# v0_1.net
KiCad netlist of a schematic drawn in EAGLE
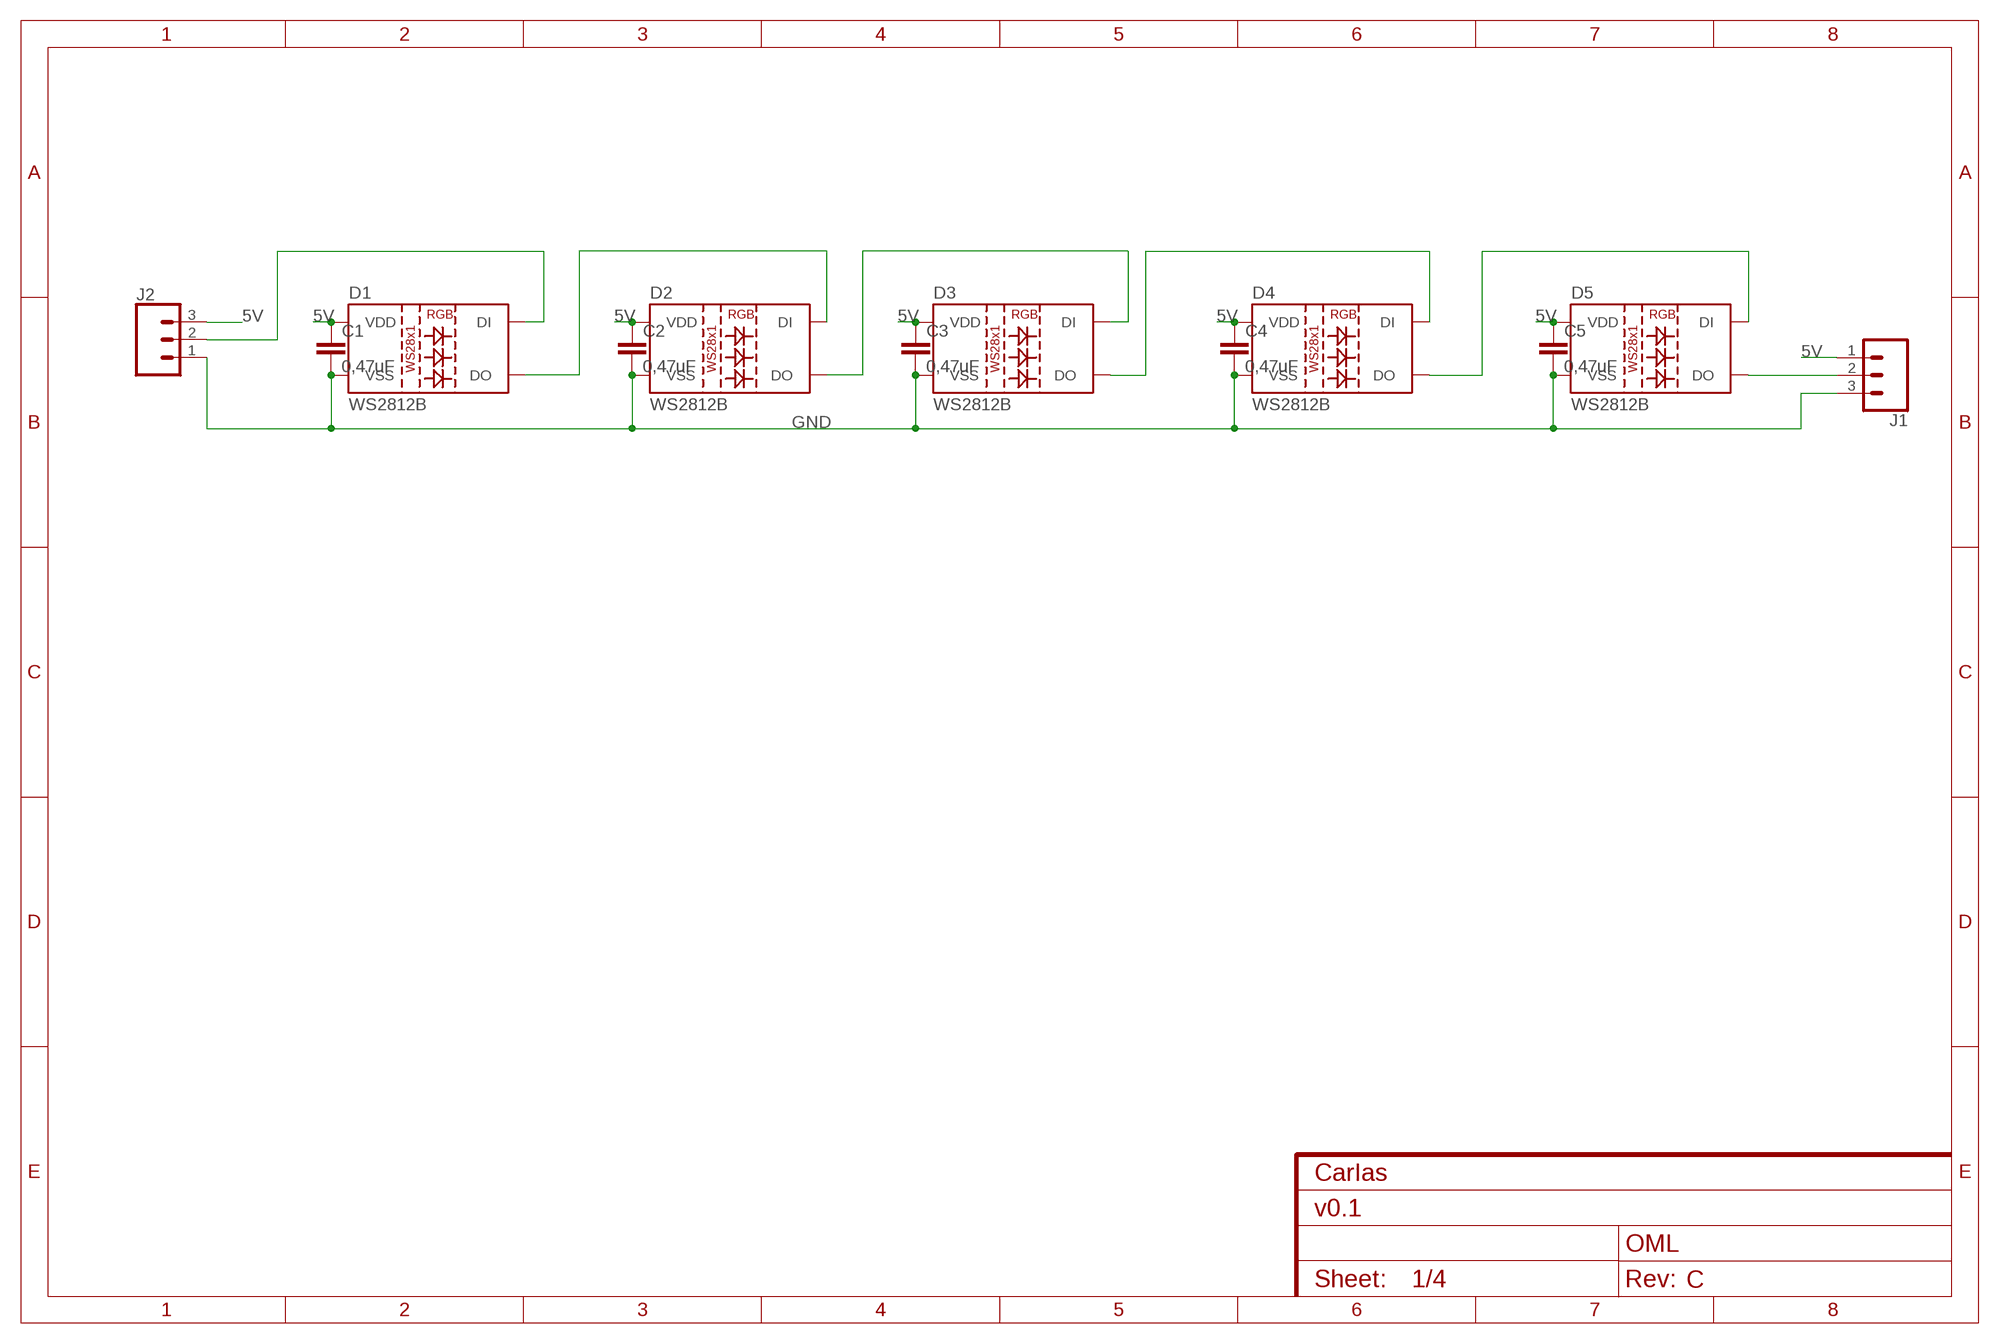
[diagram p0: schematic, sheet 1]
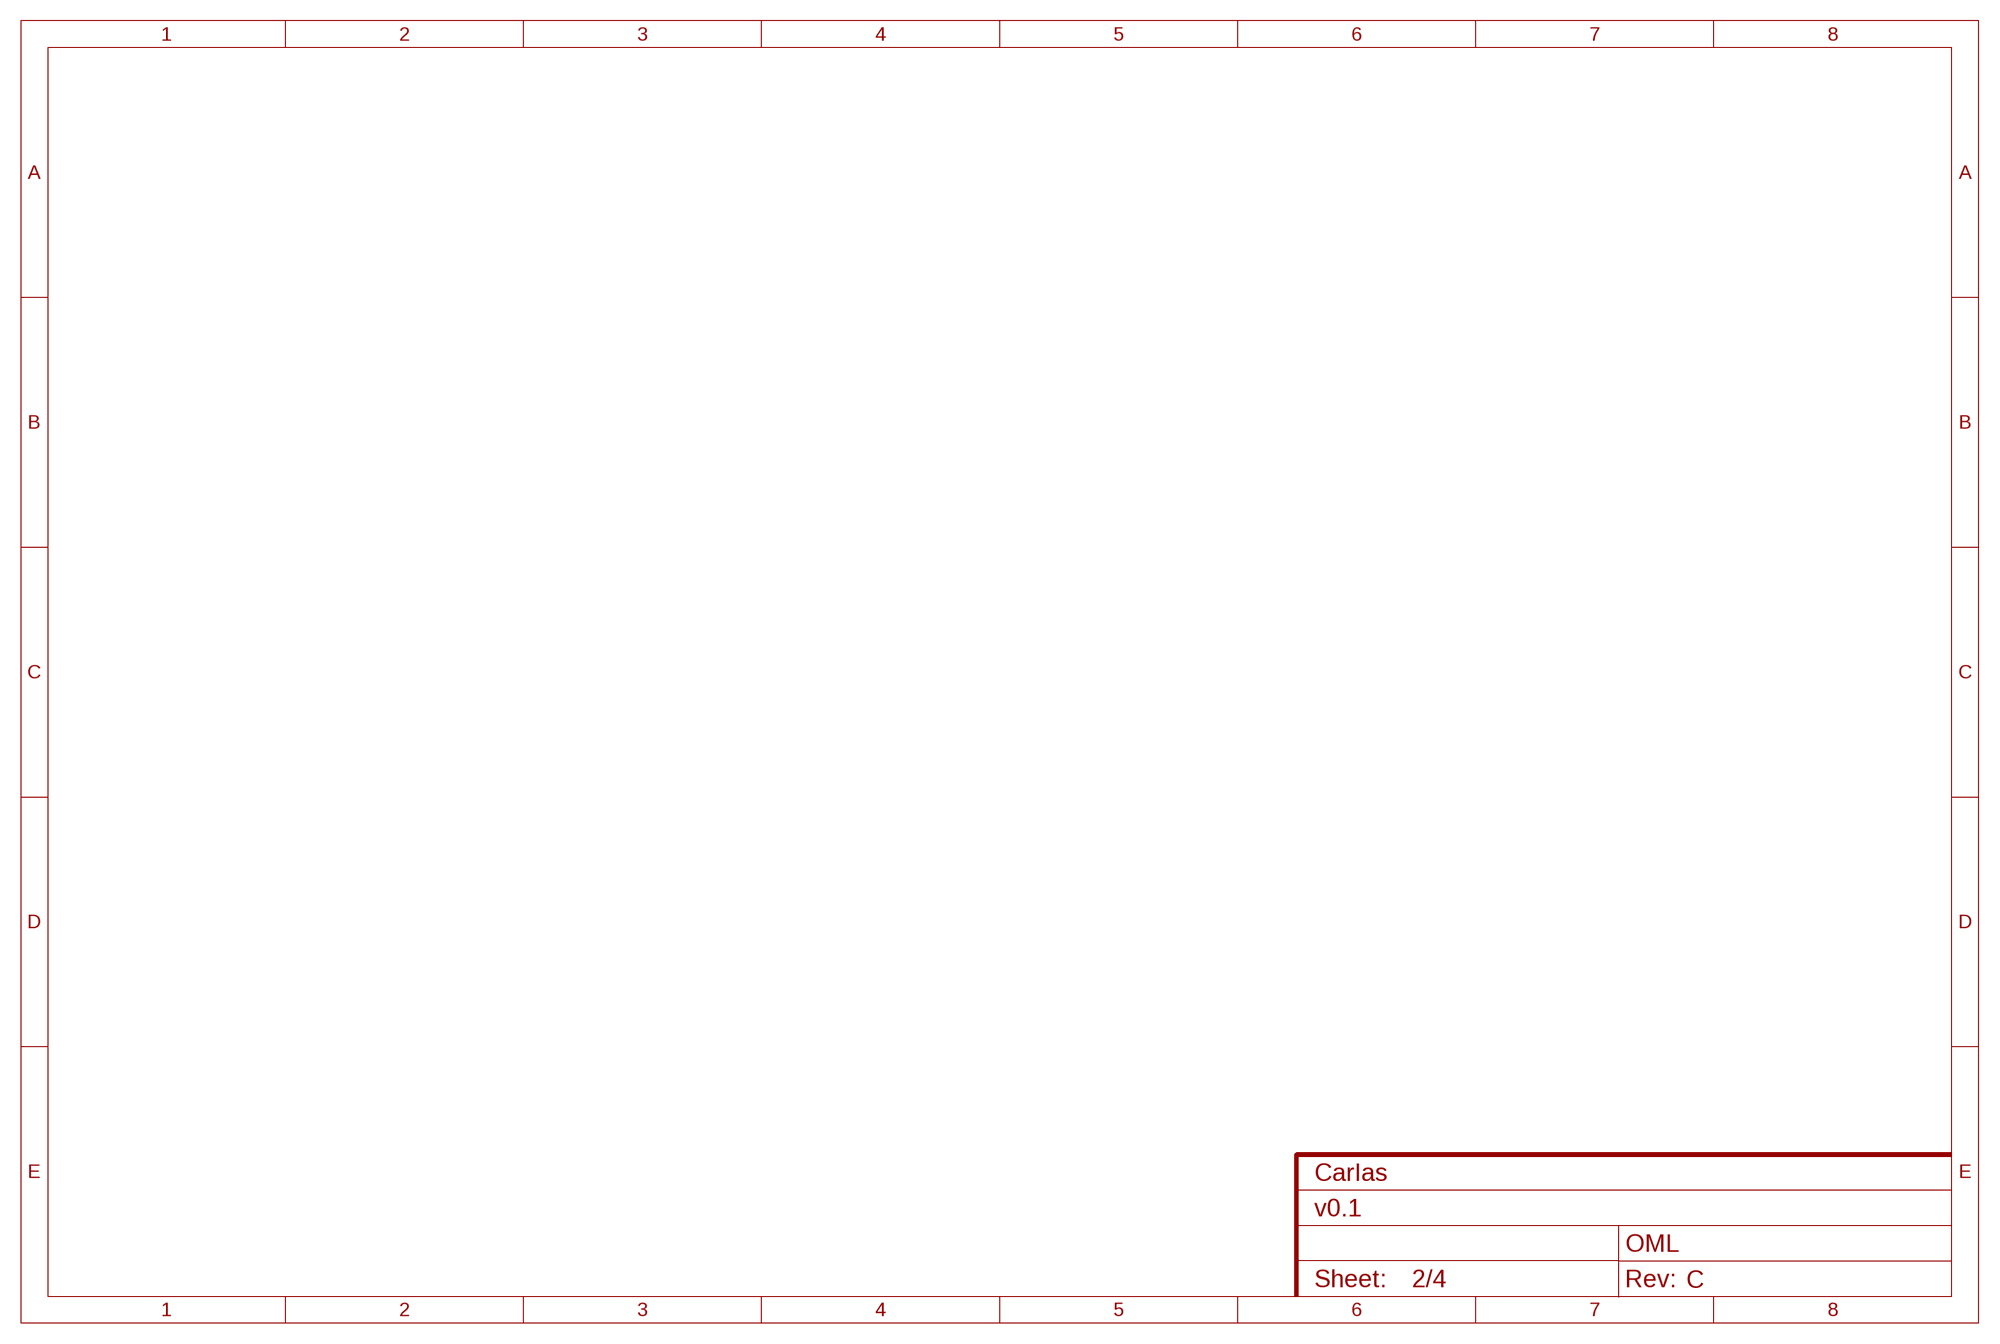
[diagram p1: schematic, sheet 2]
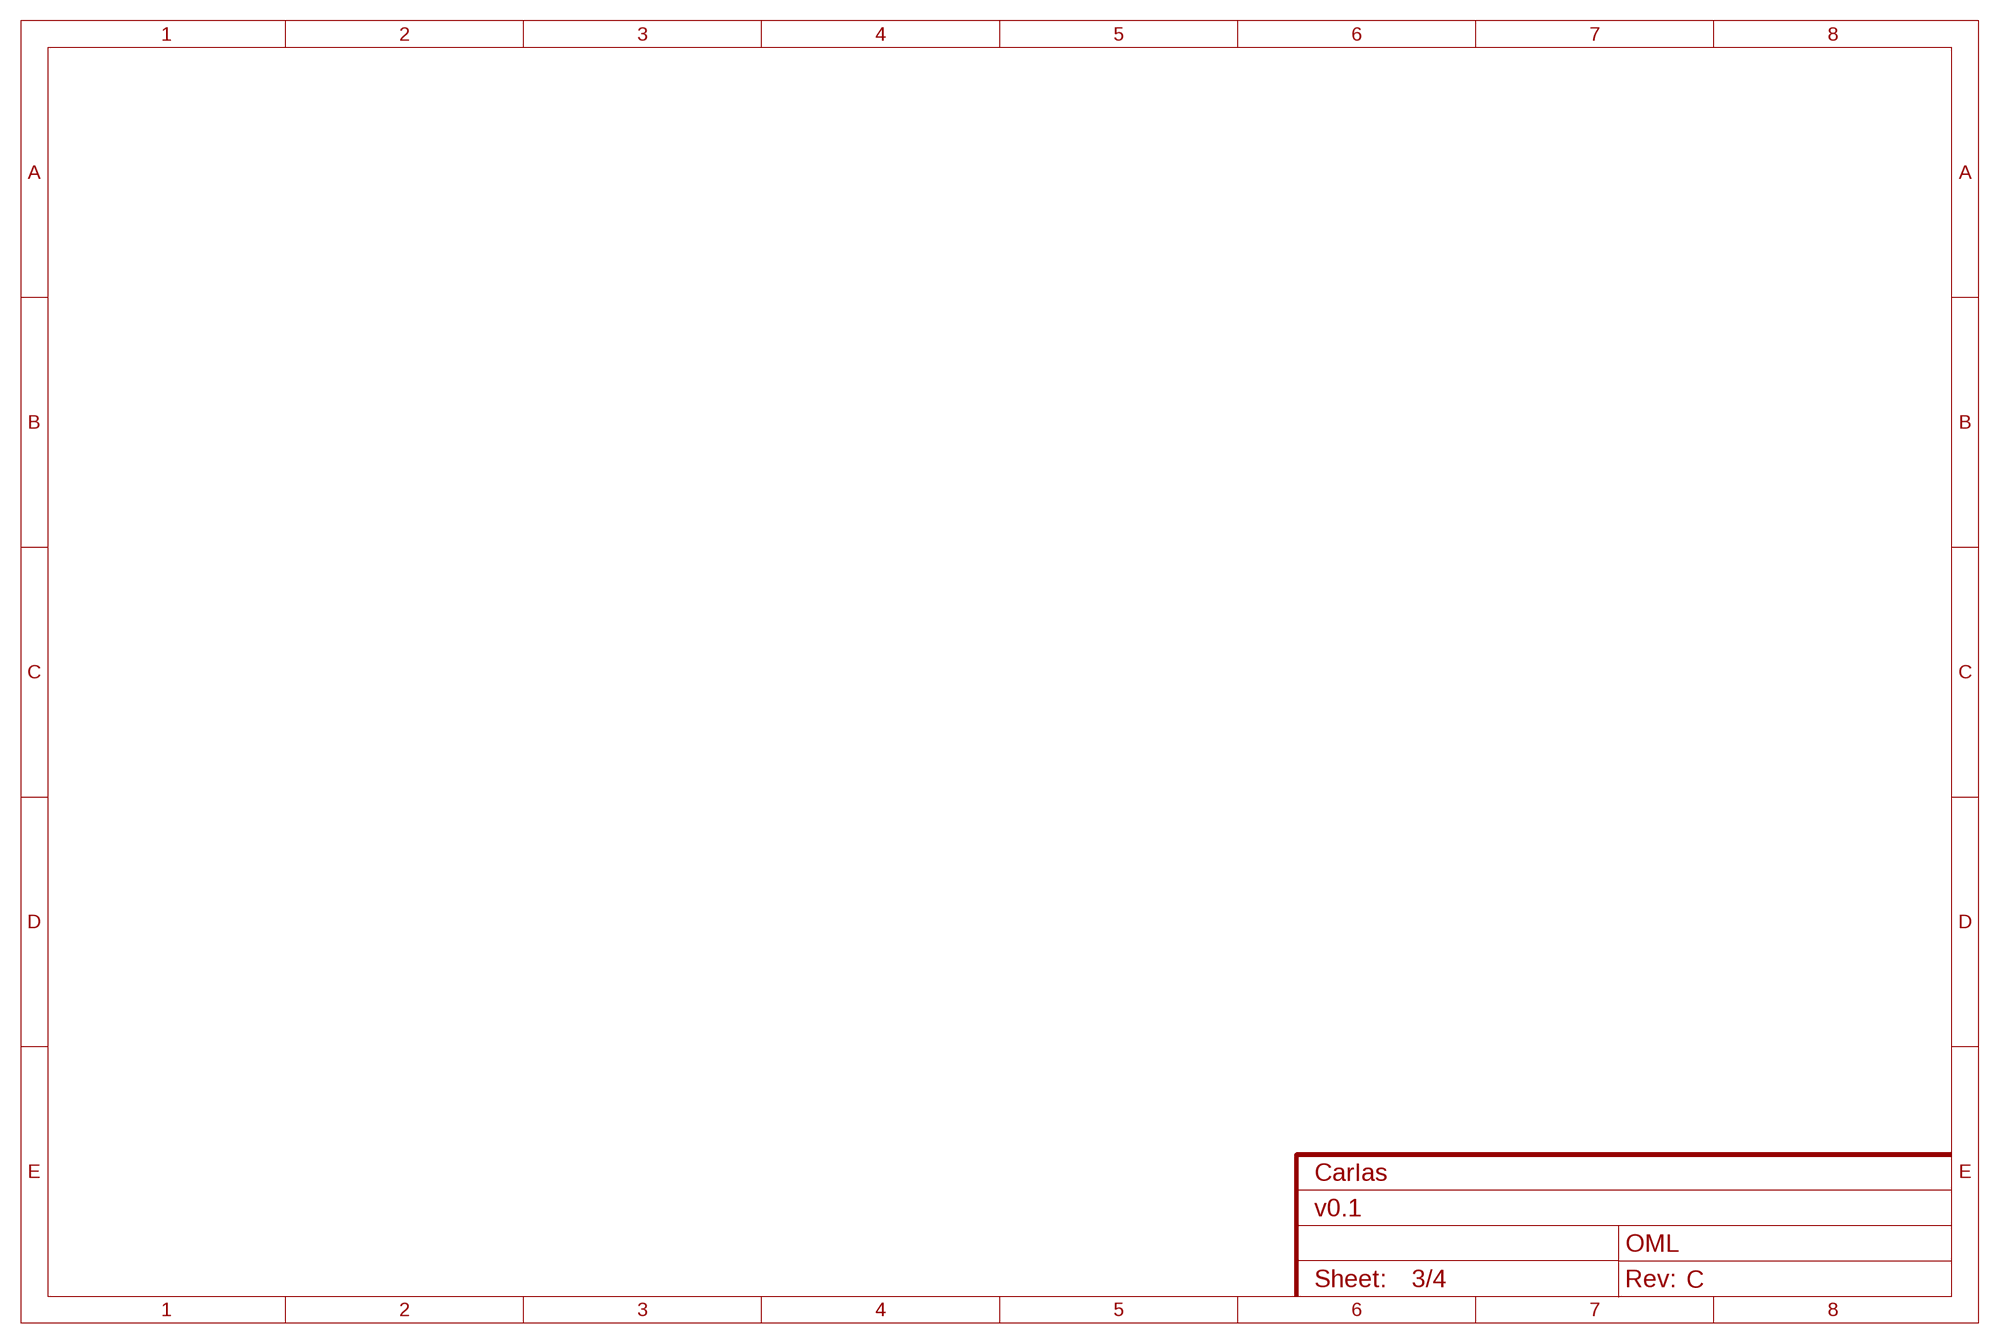
[diagram p2: schematic, sheet 3]
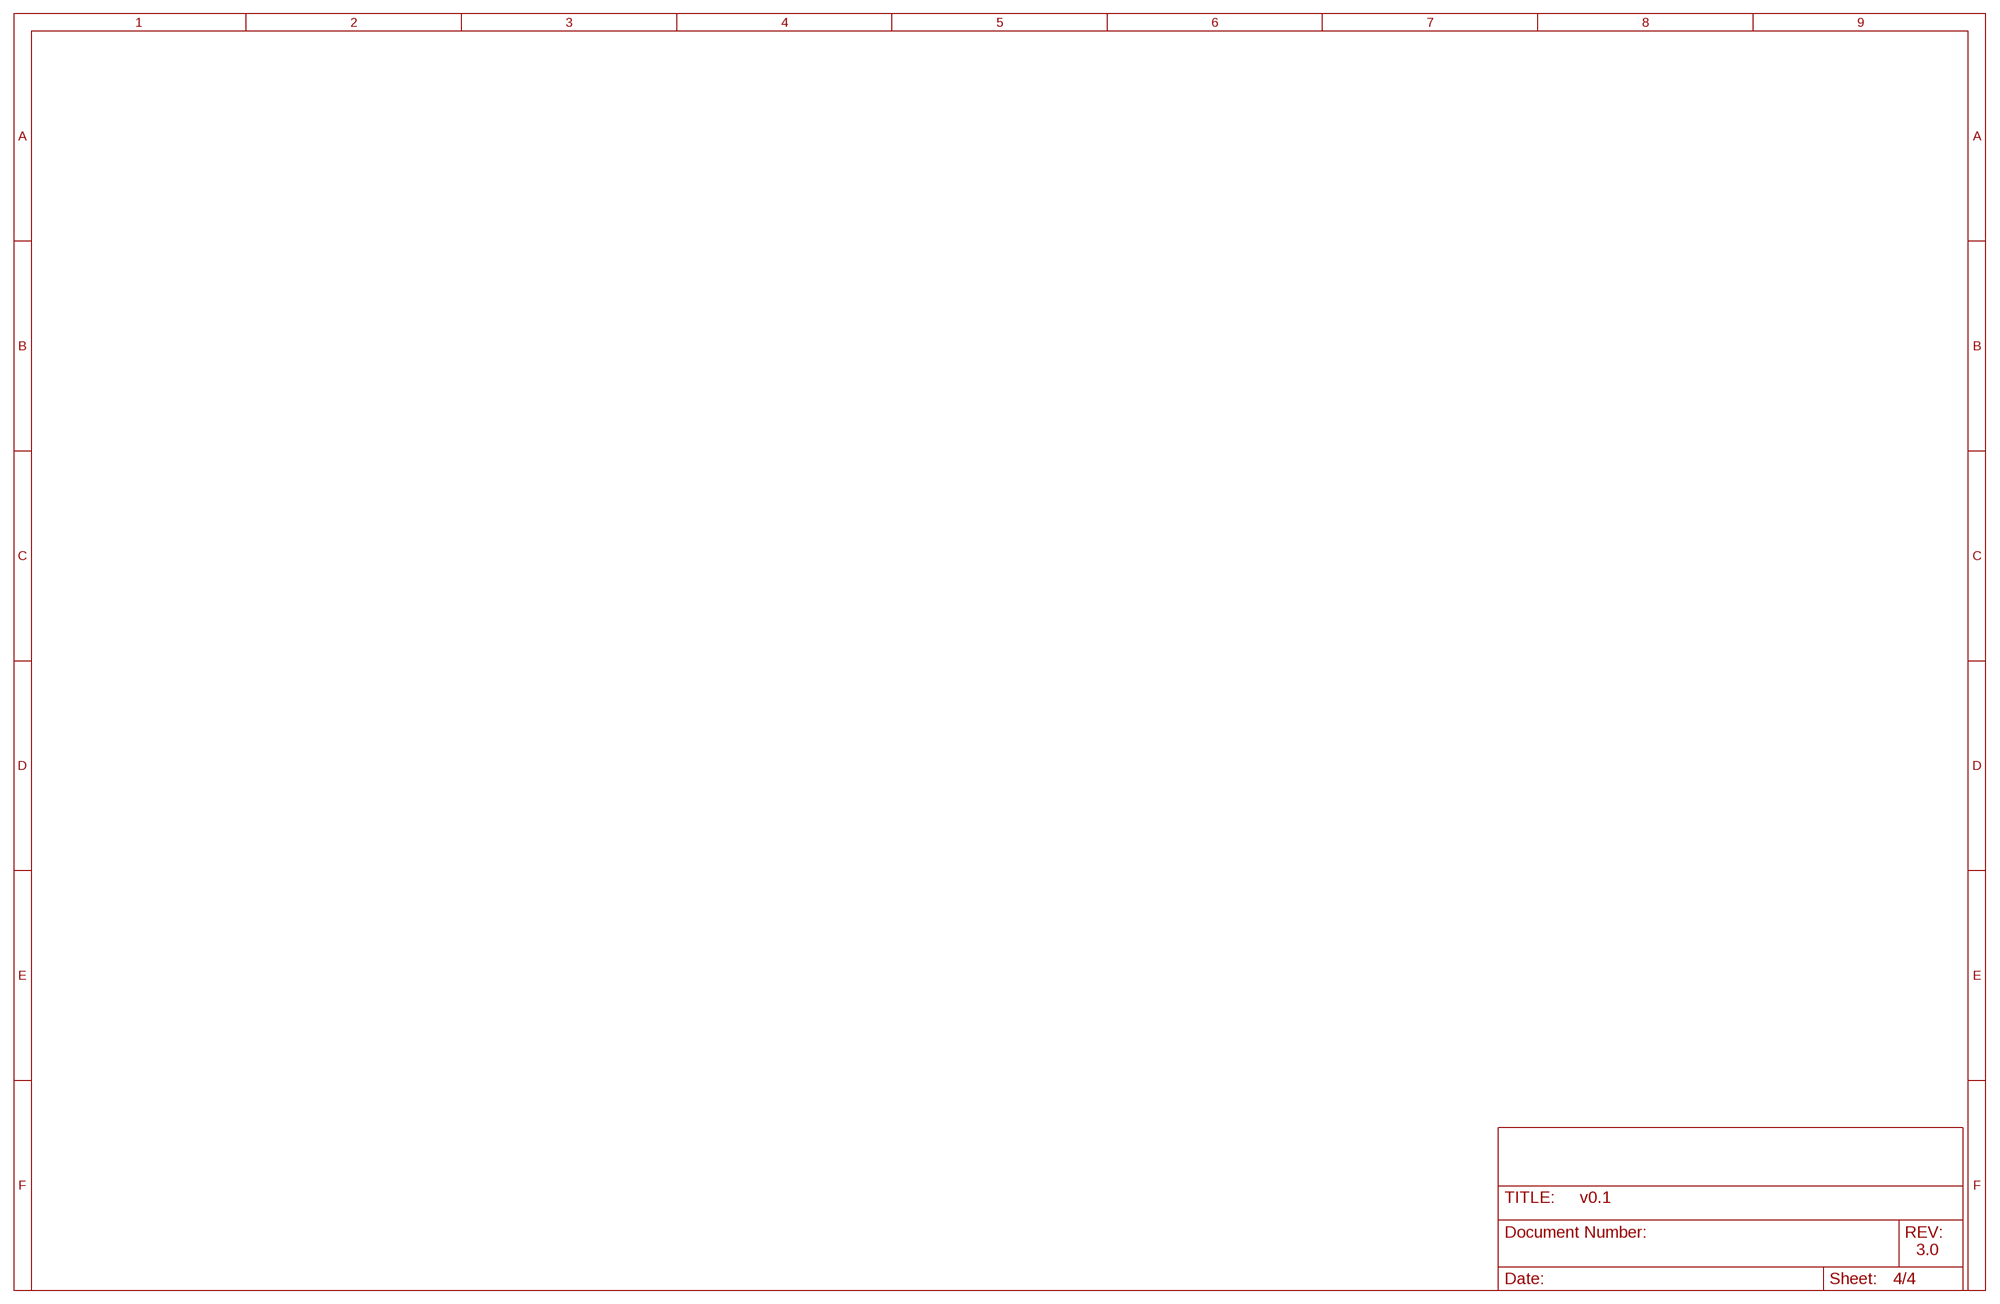
[diagram p3: schematic, sheet 4]

(export (version "E")
  (design (tool "Eeschema 10.0.6"))
  (components
    (comp (ref "C1")
      (value "0,47uF")
      (footprint "eagle-import:1206")
      (libsource (lib "eagle-import") (part "1.0UF-1206-50V-10%"))
    )
    (comp (ref "C2")
      (value "0,47uF")
      (footprint "eagle-import:1206")
      (libsource (lib "eagle-import") (part "1.0UF-1206-50V-10%"))
    )
    (comp (ref "C3")
      (value "0,47uF")
      (footprint "eagle-import:1206")
      (libsource (lib "eagle-import") (part "1.0UF-1206-50V-10%"))
    )
    (comp (ref "C4")
      (value "0,47uF")
      (footprint "eagle-import:1206")
      (libsource (lib "eagle-import") (part "1.0UF-1206-50V-10%"))
    )
    (comp (ref "C5")
      (value "0,47uF")
      (footprint "eagle-import:1206")
      (libsource (lib "eagle-import") (part "1.0UF-1206-50V-10%"))
    )
    (comp (ref "D1")
      (value "WS2812B")
      (footprint "eagle-import:WS2812B")
      (libsource (lib "eagle-import") (part "WS2812B"))
    )
    (comp (ref "D2")
      (value "WS2812B")
      (footprint "eagle-import:WS2812B")
      (libsource (lib "eagle-import") (part "WS2812B"))
    )
    (comp (ref "D3")
      (value "WS2812B")
      (footprint "eagle-import:WS2812B")
      (libsource (lib "eagle-import") (part "WS2812B"))
    )
    (comp (ref "D4")
      (value "WS2812B")
      (footprint "eagle-import:WS2812B")
      (libsource (lib "eagle-import") (part "WS2812B"))
    )
    (comp (ref "D5")
      (value "WS2812B")
      (footprint "eagle-import:WS2812B")
      (libsource (lib "eagle-import") (part "WS2812B"))
    )
    (comp (ref "J1")
      (value "CONN_03JST-PTH")
      (footprint "eagle-import:JST-3-PTH")
      (libsource (lib "eagle-import") (part "CONN_03JST-PTH"))
    )
    (comp (ref "J2")
      (value "CONN_03JST-PTH")
      (footprint "eagle-import:JST-3-PTH")
      (libsource (lib "eagle-import") (part "CONN_03JST-PTH"))
    )
  )
  (nets
    (net (code "1") (name "5V") (class "Default")
      (node (ref "C1") (pin "1") (pinfunction "1_1") (pintype "passive"))
      (node (ref "C2") (pin "1") (pinfunction "1_1") (pintype "passive"))
      (node (ref "C3") (pin "1") (pinfunction "1_1") (pintype "passive"))
      (node (ref "C4") (pin "1") (pinfunction "1_1") (pintype "passive"))
      (node (ref "C5") (pin "1") (pinfunction "1_1") (pintype "passive"))
      (node (ref "D1") (pin "1") (pinfunction "VDD_1") (pintype "bidirectional"))
      (node (ref "D2") (pin "1") (pinfunction "VDD_1") (pintype "bidirectional"))
      (node (ref "D3") (pin "1") (pinfunction "VDD_1") (pintype "bidirectional"))
      (node (ref "D4") (pin "1") (pinfunction "VDD_1") (pintype "bidirectional"))
      (node (ref "D5") (pin "1") (pinfunction "VDD_1") (pintype "bidirectional"))
      (node (ref "J1") (pin "1") (pinfunction "1_1") (pintype "passive"))
      (node (ref "J2") (pin "3") (pinfunction "3_3") (pintype "passive"))
    )
    (net (code "2") (name "GND") (class "Default")
      (node (ref "C1") (pin "2") (pinfunction "2_2") (pintype "passive"))
      (node (ref "C2") (pin "2") (pinfunction "2_2") (pintype "passive"))
      (node (ref "C3") (pin "2") (pinfunction "2_2") (pintype "passive"))
      (node (ref "C4") (pin "2") (pinfunction "2_2") (pintype "passive"))
      (node (ref "C5") (pin "2") (pinfunction "2_2") (pintype "passive"))
      (node (ref "D1") (pin "3") (pinfunction "VSS_3") (pintype "bidirectional"))
      (node (ref "D2") (pin "3") (pinfunction "VSS_3") (pintype "bidirectional"))
      (node (ref "D3") (pin "3") (pinfunction "VSS_3") (pintype "bidirectional"))
      (node (ref "D4") (pin "3") (pinfunction "VSS_3") (pintype "bidirectional"))
      (node (ref "D5") (pin "3") (pinfunction "VSS_3") (pintype "bidirectional"))
      (node (ref "J1") (pin "3") (pinfunction "3_3") (pintype "passive"))
      (node (ref "J2") (pin "1") (pinfunction "1_1") (pintype "passive"))
    )
    (net (code "3") (name "Net-(D1-DI)") (class "Default")
      (node (ref "D1") (pin "4") (pinfunction "DI_4") (pintype "bidirectional"))
      (node (ref "J2") (pin "2") (pinfunction "2_2") (pintype "passive"))
    )
    (net (code "4") (name "Net-(D1-DO)") (class "Default")
      (node (ref "D1") (pin "2") (pinfunction "DO_2") (pintype "bidirectional"))
      (node (ref "D2") (pin "4") (pinfunction "DI_4") (pintype "bidirectional"))
    )
    (net (code "5") (name "Net-(D2-DO)") (class "Default")
      (node (ref "D2") (pin "2") (pinfunction "DO_2") (pintype "bidirectional"))
      (node (ref "D3") (pin "4") (pinfunction "DI_4") (pintype "bidirectional"))
    )
    (net (code "6") (name "Net-(D3-DO)") (class "Default")
      (node (ref "D3") (pin "2") (pinfunction "DO_2") (pintype "bidirectional"))
      (node (ref "D4") (pin "4") (pinfunction "DI_4") (pintype "bidirectional"))
    )
    (net (code "7") (name "Net-(D4-DO)") (class "Default")
      (node (ref "D4") (pin "2") (pinfunction "DO_2") (pintype "bidirectional"))
      (node (ref "D5") (pin "4") (pinfunction "DI_4") (pintype "bidirectional"))
    )
    (net (code "8") (name "Net-(D5-DO)") (class "Default")
      (node (ref "D5") (pin "2") (pinfunction "DO_2") (pintype "bidirectional"))
      (node (ref "J1") (pin "2") (pinfunction "2_2") (pintype "passive"))
    )
  )
)
